# opamp-tester-mk-1_0_0.net
KiCad netlist of a schematic drawn in EAGLE
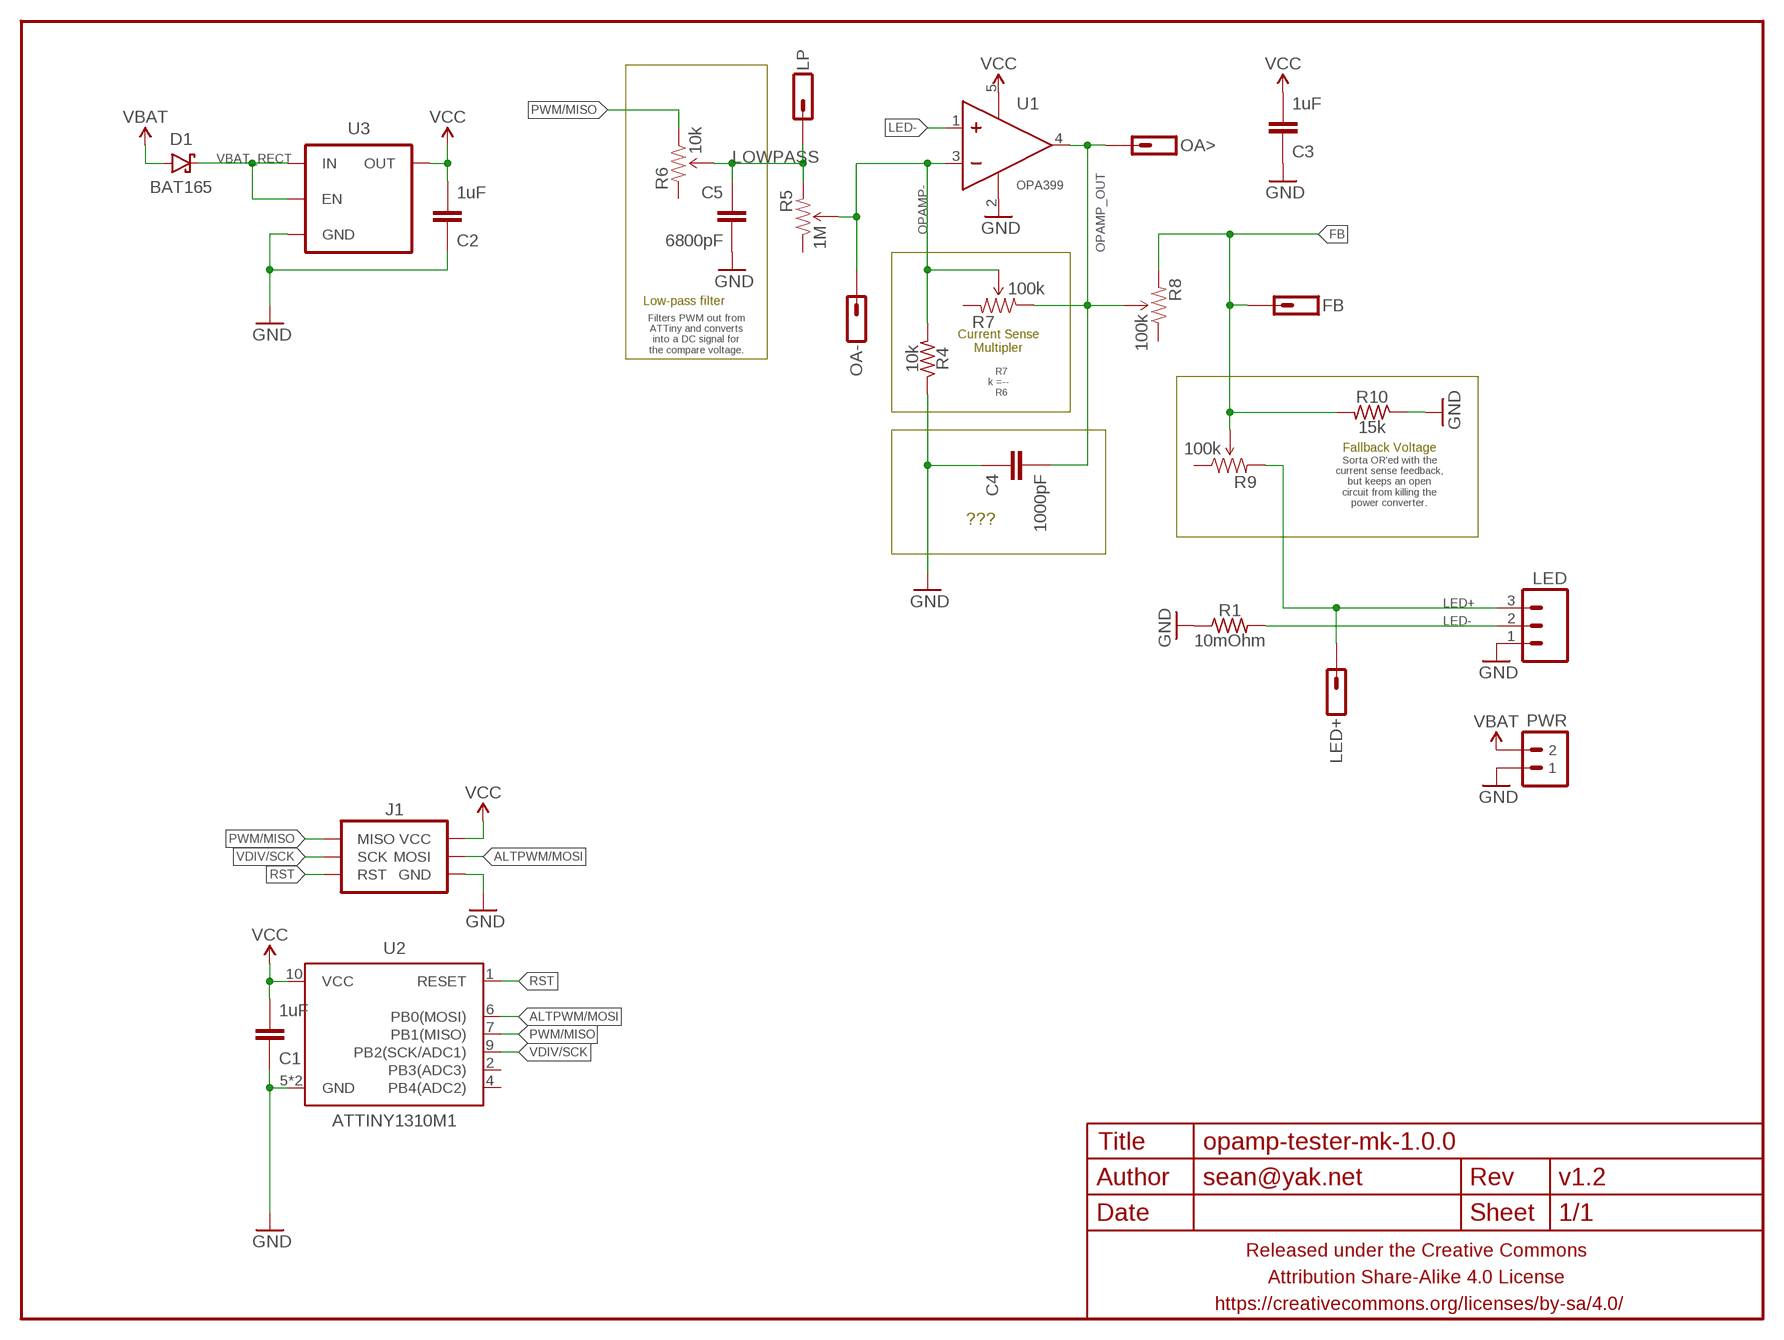
[diagram p0: schematic, sheet 1]

(export (version "E")
  (design (tool "Eeschema 10.0.6"))
  (components
    (comp (ref "C1")
      (value "1uF")
      (footprint "eagle-import:C0402")
      (libsource (lib "eagle-import") (part "CAPACITOR-CERAMICC0402"))
    )
    (comp (ref "C2")
      (value "1uF")
      (footprint "eagle-import:C0402")
      (libsource (lib "eagle-import") (part "CAPACITOR-CERAMICC0402"))
    )
    (comp (ref "C3")
      (value "1uF")
      (footprint "eagle-import:C0402")
      (libsource (lib "eagle-import") (part "CAPACITOR-CERAMICC0402"))
    )
    (comp (ref "C4")
      (value "1000pF")
      (footprint "eagle-import:C0402")
      (libsource (lib "eagle-import") (part "CAPACITOR-CERAMICC0402"))
    )
    (comp (ref "C5")
      (value "6800pF")
      (footprint "eagle-import:C0402")
      (libsource (lib "eagle-import") (part "CAPACITOR-CERAMICC0402"))
    )
    (comp (ref "D1")
      (value "BAT165")
      (footprint "eagle-import:SOD323-SCHOTTKY")
      (libsource (lib "eagle-import") (part "DIODE-SCHOTTKYSOD323"))
    )
    (comp (ref "FB")
      (value "M01PTH-0.7MM-CIR")
      (footprint "eagle-import:1X01-0.7MM-CIR")
      (libsource (lib "eagle-import") (part "M01PTH-0.7MM-CIR"))
    )
    (comp (ref "FRAME1")
      (value "FRAME-LETTERNO_PACKAGE")
      (footprint "eagle-import:DUMMY")
      (fields
        (field (name "DESIGNER") "sean@yak.net")
        (field (name "VERSION") "v1.2")
        (field (name "DESIGNER_1") "sean@yak.net")
        (field (name "VERSION_1") "v1.2")
      )
      (libsource (lib "eagle-import") (part "FRAME-LETTERNO_PACKAGE"))
    )
    (comp (ref "J1")
      (value "AVR_SPI_PRG_6SMD_TEST_POINTS")
      (footprint "eagle-import:2X3_SMD_TEST_POINTS")
      (libsource (lib "eagle-import") (part "AVR_SPI_PRG_6SMD_TEST_POINTS"))
    )
    (comp (ref "LED")
      (value "M03SCREW")
      (footprint "eagle-import:SCREWTERMINAL-3.5MM-3")
      (libsource (lib "eagle-import") (part "M03SCREW"))
    )
    (comp (ref "LED+")
      (value "M01PTH-0.7MM-CIR")
      (footprint "eagle-import:1X01-0.7MM-CIR")
      (libsource (lib "eagle-import") (part "M01PTH-0.7MM-CIR"))
    )
    (comp (ref "LP")
      (value "M01PTH-0.7MM-CIR")
      (footprint "eagle-import:1X01-0.7MM-CIR")
      (libsource (lib "eagle-import") (part "M01PTH-0.7MM-CIR"))
    )
    (comp (ref "OA-")
      (value "M01PTH-0.7MM-CIR")
      (footprint "eagle-import:1X01-0.7MM-CIR")
      (libsource (lib "eagle-import") (part "M01PTH-0.7MM-CIR"))
    )
    (comp (ref "OA>")
      (value "M01PTH-0.7MM-CIR")
      (footprint "eagle-import:1X01-0.7MM-CIR")
      (libsource (lib "eagle-import") (part "M01PTH-0.7MM-CIR"))
    )
    (comp (ref "PWR")
      (value "M02PTH-2MM")
      (footprint "eagle-import:1X02-2MM-PTH")
      (libsource (lib "eagle-import") (part "M02PTH-2MM"))
    )
    (comp (ref "R1")
      (value "10mOhm")
      (footprint "eagle-import:R1206")
      (libsource (lib "eagle-import") (part "RESISTORR1206"))
    )
    (comp (ref "R4")
      (value "10k")
      (footprint "eagle-import:R0402")
      (libsource (lib "eagle-import") (part "RESISTORR0402"))
    )
    (comp (ref "R5")
      (value "1M")
      (footprint "eagle-import:EVM3Y-LESS")
      (libsource (lib "eagle-import") (part "TRIMPOTEVM3Y-LESS"))
    )
    (comp (ref "R6")
      (value "10k")
      (footprint "eagle-import:EVM3Y-LESS")
      (libsource (lib "eagle-import") (part "TRIMPOTEVM3Y-LESS"))
    )
    (comp (ref "R7")
      (value "100k")
      (footprint "eagle-import:EVM3Y-LESS")
      (libsource (lib "eagle-import") (part "TRIMPOTEVM3Y-LESS"))
    )
    (comp (ref "R8")
      (value "100k")
      (footprint "eagle-import:EVM3Y-LESS")
      (libsource (lib "eagle-import") (part "TRIMPOTEVM3Y-LESS"))
    )
    (comp (ref "R9")
      (value "100k")
      (footprint "eagle-import:EVM3Y-LESS")
      (libsource (lib "eagle-import") (part "TRIMPOTEVM3Y-LESS"))
    )
    (comp (ref "R10")
      (value "15k")
      (footprint "eagle-import:R0402")
      (libsource (lib "eagle-import") (part "RESISTORR0402"))
    )
    (comp (ref "U1")
      (value "OPA399")
      (footprint "eagle-import:SC70")
      (libsource (lib "eagle-import") (part "OPAMPOPA333-SC-70"))
    )
    (comp (ref "U2")
      (value "ATTINY1310M1")
      (footprint "eagle-import:QFN10(2X5)")
      (libsource (lib "eagle-import") (part "ATTINY1310M1"))
    )
    (comp (ref "U3")
      (value "V_REG_ENTLV700")
      (footprint "eagle-import:SC70")
      (libsource (lib "eagle-import") (part "V_REG_ENTLV700"))
    )
  )
  (nets
    (net (code "1") (name "/LED+") (class "Default")
      (node (ref "LED") (pin "3") (pinfunction "3_3") (pintype "passive"))
      (node (ref "LED+") (pin "P$1") (pinfunction "1_P$1") (pintype "passive"))
      (node (ref "R9") (pin "E") (pinfunction "CW_E") (pintype "passive"))
    )
    (net (code "2") (name "/LOWPASS") (class "Default")
      (node (ref "C5") (pin "1") (pinfunction "1_1") (pintype "passive"))
      (node (ref "LP") (pin "P$1") (pinfunction "1_P$1") (pintype "passive"))
      (node (ref "R5") (pin "E") (pinfunction "CW_E") (pintype "passive"))
      (node (ref "R6") (pin "S") (pinfunction "WIPER_S") (pintype "passive"))
    )
    (net (code "3") (name "/OPAMP-") (class "Default")
      (node (ref "OA-") (pin "P$1") (pinfunction "1_P$1") (pintype "passive"))
      (node (ref "R4") (pin "2") (pinfunction "2_2") (pintype "passive"))
      (node (ref "R5") (pin "S") (pinfunction "WIPER_S") (pintype "passive"))
      (node (ref "R7") (pin "S") (pinfunction "WIPER_S") (pintype "passive"))
      (node (ref "U1") (pin "3") (pinfunction "IN-_3") (pintype "input"))
    )
    (net (code "4") (name "/OPAMP_OUT") (class "Default")
      (node (ref "C4") (pin "2") (pinfunction "2_2") (pintype "passive"))
      (node (ref "OA>") (pin "P$1") (pinfunction "1_P$1") (pintype "passive"))
      (node (ref "R7") (pin "A") (pinfunction "CCW_A") (pintype "passive"))
      (node (ref "R8") (pin "S") (pinfunction "WIPER_S") (pintype "passive"))
      (node (ref "U1") (pin "4") (pinfunction "OUT_4") (pintype "output"))
    )
    (net (code "5") (name "/VBAT_RECT") (class "Default")
      (node (ref "D1") (pin "C") (pinfunction "C_C") (pintype "passive"))
      (node (ref "U3") (pin "1") (pinfunction "IN_1") (pintype "input"))
      (node (ref "U3") (pin "3") (pinfunction "EN_3") (pintype "input"))
    )
    (net (code "6") (name "ALTPWM{slash}MOSI") (class "Default")
      (node (ref "J1") (pin "4") (pinfunction "MOSI_4") (pintype "passive"))
      (node (ref "U2") (pin "6") (pinfunction "PB0(MOSI)_6") (pintype "bidirectional"))
    )
    (net (code "7") (name "FB") (class "Default")
      (node (ref "FB") (pin "P$1") (pinfunction "1_P$1") (pintype "passive"))
      (node (ref "R10") (pin "2") (pinfunction "2_2") (pintype "passive"))
      (node (ref "R8") (pin "E") (pinfunction "CW_E") (pintype "passive"))
      (node (ref "R9") (pin "S") (pinfunction "WIPER_S") (pintype "passive"))
    )
    (net (code "8") (name "GND") (class "Default")
      (node (ref "C1") (pin "1") (pinfunction "1_1") (pintype "passive"))
      (node (ref "C2") (pin "1") (pinfunction "1_1") (pintype "passive"))
      (node (ref "C3") (pin "1") (pinfunction "1_1") (pintype "passive"))
      (node (ref "C4") (pin "1") (pinfunction "1_1") (pintype "passive"))
      (node (ref "C5") (pin "2") (pinfunction "2_2") (pintype "passive"))
      (node (ref "J1") (pin "6") (pinfunction "GND_6") (pintype "passive"))
      (node (ref "LED") (pin "1") (pinfunction "1_1") (pintype "passive"))
      (node (ref "PWR") (pin "P$1") (pinfunction "1_P$1") (pintype "passive"))
      (node (ref "R1") (pin "1") (pinfunction "1_1") (pintype "passive"))
      (node (ref "R10") (pin "1") (pinfunction "1_1") (pintype "passive"))
      (node (ref "R4") (pin "1") (pinfunction "1_1") (pintype "passive"))
      (node (ref "U1") (pin "2") (pinfunction "V-_2") (pintype "power_in"))
      (node (ref "U2") (pin "5") (pinfunction "GND_5") (pintype "bidirectional"))
      (node (ref "U2") (pin "PAD") (pinfunction "GND_PAD") (pintype "bidirectional"))
      (node (ref "U3") (pin "2") (pinfunction "GND_2") (pintype "input"))
    )
    (net (code "9") (name "LED-") (class "Default")
      (node (ref "LED") (pin "2") (pinfunction "2_2") (pintype "passive"))
      (node (ref "R1") (pin "2") (pinfunction "2_2") (pintype "passive"))
      (node (ref "U1") (pin "1") (pinfunction "IN+_1") (pintype "input"))
    )
    (net (code "10") (name "PWM{slash}MISO") (class "Default")
      (node (ref "J1") (pin "1") (pinfunction "MISO_1") (pintype "passive"))
      (node (ref "R6") (pin "A") (pinfunction "CCW_A") (pintype "passive"))
      (node (ref "U2") (pin "7") (pinfunction "PB1(MISO)_7") (pintype "bidirectional"))
    )
    (net (code "11") (name "RST") (class "Default")
      (node (ref "J1") (pin "5") (pinfunction "RST_5") (pintype "passive"))
      (node (ref "U2") (pin "1") (pinfunction "RESET_1") (pintype "bidirectional"))
    )
    (net (code "12") (name "VBAT") (class "Default")
      (node (ref "D1") (pin "A") (pinfunction "A_A") (pintype "passive"))
      (node (ref "PWR") (pin "P$2") (pinfunction "2_P$2") (pintype "passive"))
    )
    (net (code "13") (name "VCC") (class "Default")
      (node (ref "C1") (pin "2") (pinfunction "2_2") (pintype "passive"))
      (node (ref "C2") (pin "2") (pinfunction "2_2") (pintype "passive"))
      (node (ref "C3") (pin "2") (pinfunction "2_2") (pintype "passive"))
      (node (ref "J1") (pin "2") (pinfunction "VCC_2") (pintype "passive"))
      (node (ref "U1") (pin "5") (pinfunction "V+_5") (pintype "power_in"))
      (node (ref "U2") (pin "10") (pinfunction "VCC_10") (pintype "bidirectional"))
      (node (ref "U3") (pin "5") (pinfunction "OUT_5") (pintype "passive"))
    )
    (net (code "14") (name "VDIV{slash}SCK") (class "Default")
      (node (ref "J1") (pin "3") (pinfunction "SCK_3") (pintype "passive"))
      (node (ref "U2") (pin "9") (pinfunction "PB2(SCK/ADC1)_9") (pintype "bidirectional"))
    )
    (net (code "15") (name "unconnected-(R5-CCW-PadA)") (class "Default")
      (node (ref "R5") (pin "A") (pinfunction "CCW_A") (pintype "passive"))
    )
    (net (code "16") (name "unconnected-(R6-CW-PadE)") (class "Default")
      (node (ref "R6") (pin "E") (pinfunction "CW_E") (pintype "passive"))
    )
    (net (code "17") (name "unconnected-(R7-CW-PadE)") (class "Default")
      (node (ref "R7") (pin "E") (pinfunction "CW_E") (pintype "passive"))
    )
    (net (code "18") (name "unconnected-(R8-CCW-PadA)") (class "Default")
      (node (ref "R8") (pin "A") (pinfunction "CCW_A") (pintype "passive"))
    )
    (net (code "19") (name "unconnected-(R9-CCW-PadA)") (class "Default")
      (node (ref "R9") (pin "A") (pinfunction "CCW_A") (pintype "passive"))
    )
    (net (code "20") (name "unconnected-(U2-PB3(ADC3)-Pad2)") (class "Default")
      (node (ref "U2") (pin "2") (pinfunction "PB3(ADC3)_2") (pintype "bidirectional"))
    )
    (net (code "21") (name "unconnected-(U2-PB4(ADC2)-Pad4)") (class "Default")
      (node (ref "U2") (pin "4") (pinfunction "PB4(ADC2)_4") (pintype "bidirectional"))
    )
  )
)
